# Wrigley_V1.net
KiCad netlist of a schematic drawn in EAGLE
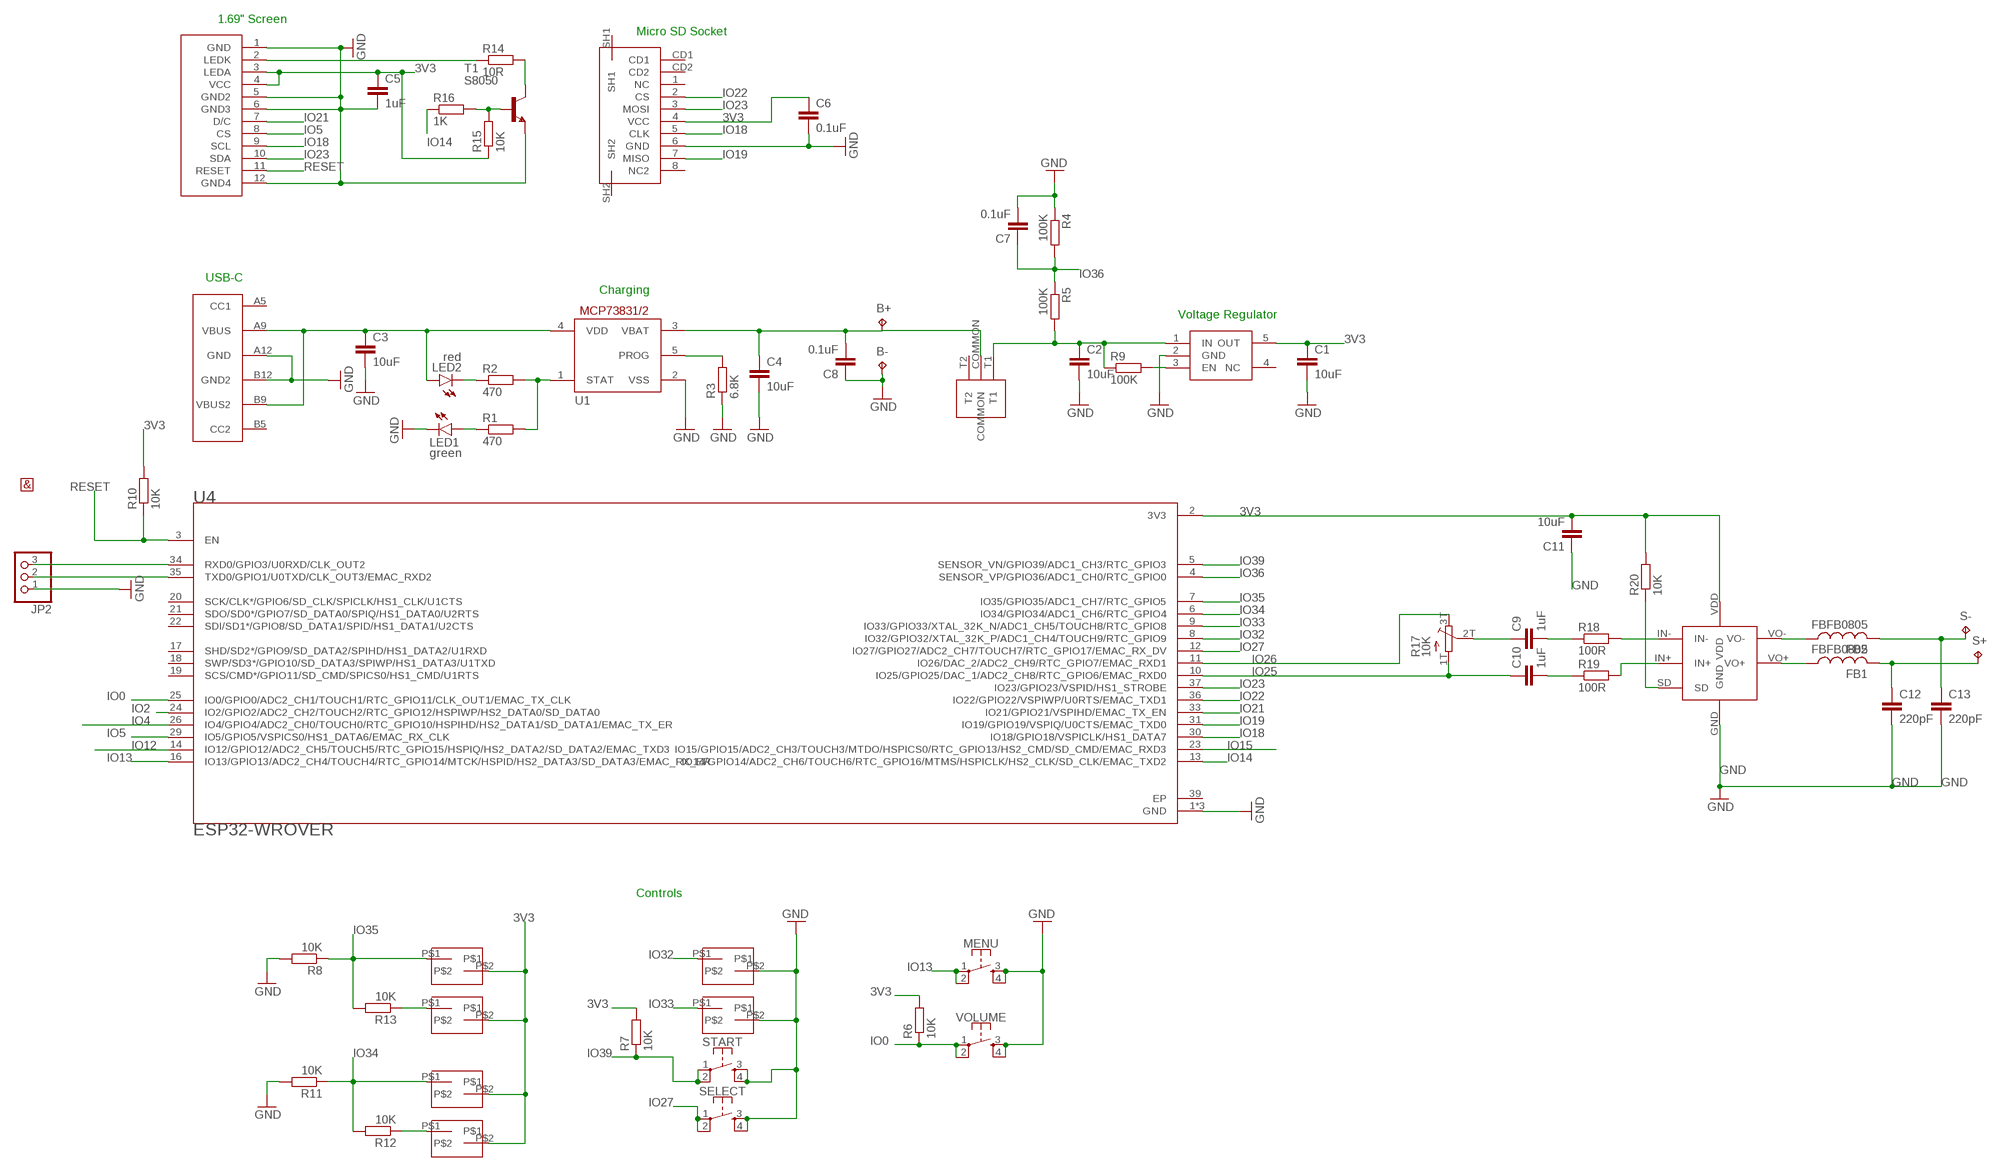
[diagram p0: schematic, sheet 1]

(export (version "E")
  (design (tool "Eeschema 10.0.6"))
  (components
    (comp (ref "A")
      (value "POCKET-BUTTONS-BIG")
      (footprint "eagle-import:POCKET-MEMBRANE-BIG")
      (libsource (lib "eagle-import") (part "POCKET-BUTTONS-BIG"))
    )
    (comp (ref "B")
      (value "POCKET-BUTTONS-BIG")
      (footprint "eagle-import:POCKET-MEMBRANE-BIG")
      (libsource (lib "eagle-import") (part "POCKET-BUTTONS-BIG"))
    )
    (comp (ref "B+")
      (value "TPTP20R")
      (footprint "eagle-import:TP20R")
      (libsource (lib "eagle-import") (part "TPTP20R"))
    )
    (comp (ref "B-")
      (value "TPTP20R")
      (footprint "eagle-import:TP20R")
      (libsource (lib "eagle-import") (part "TPTP20R"))
    )
    (comp (ref "C1")
      (value "10uF")
      (footprint "eagle-import:C0805")
      (libsource (lib "eagle-import") (part "C-EUC0805"))
    )
    (comp (ref "C2")
      (value "10uF")
      (footprint "eagle-import:C0805")
      (libsource (lib "eagle-import") (part "C-EUC0805"))
    )
    (comp (ref "C3")
      (value "10uF")
      (footprint "eagle-import:C0805")
      (libsource (lib "eagle-import") (part "C-EUC0805"))
    )
    (comp (ref "C4")
      (value "10uF")
      (footprint "eagle-import:C0805")
      (libsource (lib "eagle-import") (part "C-EUC0805"))
    )
    (comp (ref "C5")
      (value "1uF")
      (footprint "eagle-import:C0805")
      (libsource (lib "eagle-import") (part "C-EUC0805"))
    )
    (comp (ref "C6")
      (value "0.1uF")
      (footprint "eagle-import:C0805")
      (libsource (lib "eagle-import") (part "C-EUC0805"))
    )
    (comp (ref "C7")
      (value "0.1uF")
      (footprint "eagle-import:C0805")
      (libsource (lib "eagle-import") (part "C-EUC0805"))
    )
    (comp (ref "C8")
      (value "0.1uF")
      (footprint "eagle-import:C0805")
      (libsource (lib "eagle-import") (part "C-EUC0805"))
    )
    (comp (ref "C9")
      (value "1uF")
      (footprint "eagle-import:C0805")
      (libsource (lib "eagle-import") (part "C-EUC0805"))
    )
    (comp (ref "C10")
      (value "1uF")
      (footprint "eagle-import:C0805")
      (libsource (lib "eagle-import") (part "C-EUC0805"))
    )
    (comp (ref "C11")
      (value "10uF")
      (footprint "eagle-import:C0805")
      (libsource (lib "eagle-import") (part "C-EUC0805"))
    )
    (comp (ref "C12")
      (value "220pF")
      (footprint "eagle-import:C0805")
      (libsource (lib "eagle-import") (part "C-EUC0805"))
    )
    (comp (ref "C13")
      (value "220pF")
      (footprint "eagle-import:C0805")
      (libsource (lib "eagle-import") (part "C-EUC0805"))
    )
    (comp (ref "DOWN")
      (value "POCKET-BUTTONS-BIG")
      (footprint "eagle-import:POCKET-MEMBRANE-BIG")
      (libsource (lib "eagle-import") (part "POCKET-BUTTONS-BIG"))
    )
    (comp (ref "FB1")
      (value "FBFB0805")
      (footprint "eagle-import:0805")
      (libsource (lib "eagle-import") (part "FBFB0805"))
    )
    (comp (ref "FB2")
      (value "FBFB0805")
      (footprint "eagle-import:0805")
      (libsource (lib "eagle-import") (part "FBFB0805"))
    )
    (comp (ref "JP2")
      (value "PINHD-1X03_2.54-S")
      (footprint "eagle-import:1X03-S")
      (libsource (lib "eagle-import") (part "PINHD-1X03_2.54-S"))
    )
    (comp (ref "LED1")
      (value "green")
      (footprint "eagle-import:CHIP-LED0805")
      (libsource (lib "eagle-import") (part "LEDCHIP-LED0805"))
    )
    (comp (ref "LED2")
      (value "red")
      (footprint "eagle-import:CHIP-LED0805")
      (libsource (lib "eagle-import") (part "LEDCHIP-LED0805"))
    )
    (comp (ref "LEFT")
      (value "POCKET-BUTTONS-BIG")
      (footprint "eagle-import:POCKET-MEMBRANE-BIG")
      (libsource (lib "eagle-import") (part "POCKET-BUTTONS-BIG"))
    )
    (comp (ref "MENU")
      (value "MOMENTARY-SWITCH-SPST-2-SMD-5.2MM")
      (footprint "eagle-import:TACTILE_SWITCH_SMD_5.2MM")
      (libsource (lib "eagle-import") (part "MOMENTARY-SWITCH-SPST-2-SMD-5.2MM"))
    )
    (comp (ref "R1")
      (value "470")
      (footprint "eagle-import:R0805")
      (libsource (lib "eagle-import") (part "resistor_348_R-EU_R0805"))
    )
    (comp (ref "R2")
      (value "470")
      (footprint "eagle-import:R0805")
      (libsource (lib "eagle-import") (part "resistor_348_R-EU_R0805"))
    )
    (comp (ref "R3")
      (value "6.8K")
      (footprint "eagle-import:R0805")
      (libsource (lib "eagle-import") (part "resistor_348_R-EU_R0805"))
    )
    (comp (ref "R4")
      (value "100K")
      (footprint "eagle-import:M0805")
      (libsource (lib "eagle-import") (part "resistor_348_R-EU_M0805"))
    )
    (comp (ref "R5")
      (value "100K")
      (footprint "eagle-import:M0805")
      (libsource (lib "eagle-import") (part "resistor_348_R-EU_M0805"))
    )
    (comp (ref "R6")
      (value "10K")
      (footprint "eagle-import:M0805")
      (libsource (lib "eagle-import") (part "resistor_348_R-EU_M0805"))
    )
    (comp (ref "R7")
      (value "10K")
      (footprint "eagle-import:M0805")
      (libsource (lib "eagle-import") (part "resistor_348_R-EU_M0805"))
    )
    (comp (ref "R8")
      (value "10K")
      (footprint "eagle-import:M0805")
      (libsource (lib "eagle-import") (part "resistor_348_R-EU_M0805"))
    )
    (comp (ref "R9")
      (value "100K")
      (footprint "eagle-import:M0805")
      (libsource (lib "eagle-import") (part "resistor_348_R-EU_M0805"))
    )
    (comp (ref "R10")
      (value "10K")
      (footprint "eagle-import:M0805")
      (libsource (lib "eagle-import") (part "resistor_348_R-EU_M0805"))
    )
    (comp (ref "R11")
      (value "10K")
      (footprint "eagle-import:M0805")
      (libsource (lib "eagle-import") (part "resistor_348_R-EU_M0805"))
    )
    (comp (ref "R12")
      (value "10K")
      (footprint "eagle-import:M0805")
      (libsource (lib "eagle-import") (part "resistor_348_R-EU_M0805"))
    )
    (comp (ref "R13")
      (value "10K")
      (footprint "eagle-import:M0805")
      (libsource (lib "eagle-import") (part "resistor_348_R-EU_M0805"))
    )
    (comp (ref "R14")
      (value "10R")
      (footprint "eagle-import:M0805")
      (libsource (lib "eagle-import") (part "resistor_348_R-EU_M0805"))
    )
    (comp (ref "R15")
      (value "10K")
      (footprint "eagle-import:M0805")
      (libsource (lib "eagle-import") (part "resistor_348_R-EU_M0805"))
    )
    (comp (ref "R16")
      (value "1K")
      (footprint "eagle-import:M0805")
      (libsource (lib "eagle-import") (part "resistor_348_R-EU_M0805"))
    )
    (comp (ref "R17")
      (value "10K")
      (footprint "eagle-import:SLIDE-POT-RS08U11AZ001")
      (libsource (lib "eagle-import") (part "TRIMPOT"))
    )
    (comp (ref "R18")
      (value "100R")
      (footprint "eagle-import:R0805")
      (libsource (lib "eagle-import") (part "R-EU_R0805"))
    )
    (comp (ref "R19")
      (value "100R")
      (footprint "eagle-import:R0805")
      (libsource (lib "eagle-import") (part "R-EU_R0805"))
    )
    (comp (ref "R20")
      (value "10K")
      (footprint "eagle-import:R0805")
      (libsource (lib "eagle-import") (part "R-EU_R0805"))
    )
    (comp (ref "RIGHT")
      (value "POCKET-BUTTONS-BIG")
      (footprint "eagle-import:POCKET-MEMBRANE-BIG")
      (libsource (lib "eagle-import") (part "POCKET-BUTTONS-BIG"))
    )
    (comp (ref "S+")
      (value "TPTP20R")
      (footprint "eagle-import:TP20R")
      (libsource (lib "eagle-import") (part "TPTP20R"))
    )
    (comp (ref "S-")
      (value "TPTP20R")
      (footprint "eagle-import:TP20R")
      (libsource (lib "eagle-import") (part "TPTP20R"))
    )
    (comp (ref "SELECT")
      (value "MOMENTARY-SWITCH-SPST-2-SMD-5.2MM")
      (footprint "eagle-import:TACTILE_SWITCH_SMD_5.2MM")
      (libsource (lib "eagle-import") (part "MOMENTARY-SWITCH-SPST-2-SMD-5.2MM"))
    )
    (comp (ref "START")
      (value "MOMENTARY-SWITCH-SPST-2-SMD-5.2MM")
      (footprint "eagle-import:TACTILE_SWITCH_SMD_5.2MM")
      (libsource (lib "eagle-import") (part "MOMENTARY-SWITCH-SPST-2-SMD-5.2MM"))
    )
    (comp (ref "T1")
      (value "S8050")
      (footprint "eagle-import:SOT23-BEC")
      (libsource (lib "eagle-import") (part "S8050"))
    )
    (comp (ref "U$1")
      (value "MICROSD-SOCKET-RISTRETTONO-HOLES")
      (footprint "eagle-import:MICROSD-SOCKET-WRIGLEY")
      (libsource (lib "eagle-import") (part "MICROSD-SOCKET-RISTRETTONO-HOLES"))
    )
    (comp (ref "U$3")
      (value "1.69-INCH-SCREEN-ROUNDED")
      (footprint "eagle-import:1.69-INCH-SCREEN-ROUNDED")
      (libsource (lib "eagle-import") (part "1.69-INCH-SCREEN-ROUNDED"))
    )
    (comp (ref "U$5")
      (value "NULL2-SWITCH")
      (footprint "eagle-import:NULL2-SWITCH")
      (libsource (lib "eagle-import") (part "NULL2-SWITCH"))
    )
    (comp (ref "U$8")
      (value "USB-C-6PIN")
      (footprint "eagle-import:USB-C-6PIN")
      (libsource (lib "eagle-import") (part "USB-C-6PIN"))
    )
    (comp (ref "U$9")
      (value "AMP-HALF")
      (footprint "eagle-import:AMP-HALF")
      (libsource (lib "eagle-import") (part "AMP-HALF"))
    )
    (comp (ref "U1")
      (value "MCP73831/OT")
      (footprint "eagle-import:SOT23-5L")
      (libsource (lib "eagle-import") (part "MCP73831/OT"))
    )
    (comp (ref "U2")
      (value "AP2112-REGULATORWRIGLEY")
      (footprint "eagle-import:SOT23-5L")
      (libsource (lib "eagle-import") (part "AP2112-REGULATORWRIGLEY"))
    )
    (comp (ref "U3")
      (value "PAM8302A")
      (footprint "eagle-import:PAM8302A-SOP8")
      (libsource (lib "eagle-import") (part "PAM8302A"))
    )
    (comp (ref "U4")
      (value "ESP32-WROVER")
      (footprint "eagle-import:XCVR-ESP32-WROVER")
      (libsource (lib "eagle-import") (part "ESP32-WROVER"))
    )
    (comp (ref "UP")
      (value "POCKET-BUTTONS-BIG")
      (footprint "eagle-import:POCKET-MEMBRANE-BIG")
      (libsource (lib "eagle-import") (part "POCKET-BUTTONS-BIG"))
    )
    (comp (ref "VOLUME")
      (value "MOMENTARY-SWITCH-SPST-2-SMD-5.2MM")
      (footprint "eagle-import:TACTILE_SWITCH_SMD_5.2MM")
      (libsource (lib "eagle-import") (part "MOMENTARY-SWITCH-SPST-2-SMD-5.2MM"))
    )
  )
  (nets
    (net (code "1") (name "/3V3") (class "Default")
      (node (ref "C1") (pin "1") (pinfunction "1_1") (pintype "passive"))
      (node (ref "C11") (pin "2") (pinfunction "2_2") (pintype "passive"))
      (node (ref "C5") (pin "1") (pinfunction "1_1") (pintype "passive"))
      (node (ref "C6") (pin "1") (pinfunction "1_1") (pintype "passive"))
      (node (ref "DOWN") (pin "P$2") (pinfunction "P$2_P$2") (pintype "bidirectional"))
      (node (ref "LEFT") (pin "P$2") (pinfunction "P$2_P$2") (pintype "bidirectional"))
      (node (ref "R10") (pin "2") (pinfunction "2_2") (pintype "passive"))
      (node (ref "R15") (pin "1") (pinfunction "1_1") (pintype "passive"))
      (node (ref "R20") (pin "2") (pinfunction "2_2") (pintype "passive"))
      (node (ref "R6") (pin "2") (pinfunction "2_2") (pintype "passive"))
      (node (ref "R7") (pin "2") (pinfunction "2_2") (pintype "passive"))
      (node (ref "RIGHT") (pin "P$2") (pinfunction "P$2_P$2") (pintype "bidirectional"))
      (node (ref "U$1") (pin "4") (pinfunction "VCC_4") (pintype "bidirectional"))
      (node (ref "U$3") (pin "3") (pinfunction "LEDA_3") (pintype "bidirectional"))
      (node (ref "U$3") (pin "4") (pinfunction "VCC_4") (pintype "bidirectional"))
      (node (ref "U2") (pin "5") (pinfunction "OUT_5") (pintype "bidirectional"))
      (node (ref "U3") (pin "VDD") (pinfunction "VDD_VDD") (pintype "bidirectional"))
      (node (ref "U4") (pin "2") (pinfunction "3V3_2") (pintype "power_in"))
      (node (ref "UP") (pin "P$2") (pinfunction "P$2_P$2") (pintype "bidirectional"))
    )
    (net (code "2") (name "/EP") (class "Default")
      (node (ref "U4") (pin "39") (pinfunction "EP_39") (pintype "power_in"))
    )
    (net (code "3") (name "/IO0") (class "Default")
      (node (ref "R6") (pin "1") (pinfunction "1_1") (pintype "passive"))
      (node (ref "U4") (pin "25") (pinfunction "IO0/GPIO0/ADC2_CH1/TOUCH1/RTC_GPIO11/CLK_OUT1/EMAC_TX_CLK_25") (pintype "bidirectional"))
      (node (ref "VOLUME") (pin "1") (pinfunction "1_1") (pintype "passive"))
      (node (ref "VOLUME") (pin "2") (pinfunction "2_2") (pintype "passive"))
    )
    (net (code "4") (name "/IO2") (class "Default")
      (node (ref "U4") (pin "24") (pinfunction "IO2/GPIO2/ADC2_CH2/TOUCH2/RTC_GPIO12/HSPIWP/HS2_DATA0/SD_DATA0_24") (pintype "bidirectional"))
    )
    (net (code "5") (name "/IO4") (class "Default")
      (node (ref "U4") (pin "26") (pinfunction "IO4/GPIO4/ADC2_CH0/TOUCH0/RTC_GPIO10/HSPIHD/HS2_DATA1/SD_DATA1/EMAC_TX_ER_26") (pintype "bidirectional"))
    )
    (net (code "6") (name "/IO5") (class "Default")
      (node (ref "U$3") (pin "8") (pinfunction "CS_8") (pintype "bidirectional"))
      (node (ref "U4") (pin "29") (pinfunction "IO5/GPIO5/VSPICS0/HS1_DATA6/EMAC_RX_CLK_29") (pintype "bidirectional"))
    )
    (net (code "7") (name "/IO12") (class "Default")
      (node (ref "U4") (pin "14") (pinfunction "IO12/GPIO12/ADC2_CH5/TOUCH5/RTC_GPIO15/HSPIQ/HS2_DATA2/SD_DATA2/EMAC_TXD3_14") (pintype "bidirectional"))
    )
    (net (code "8") (name "/IO13") (class "Default")
      (node (ref "MENU") (pin "1") (pinfunction "1_1") (pintype "passive"))
      (node (ref "MENU") (pin "2") (pinfunction "2_2") (pintype "passive"))
      (node (ref "U4") (pin "16") (pinfunction "IO13/GPIO13/ADC2_CH4/TOUCH4/RTC_GPIO14/MTCK/HSPID/HS2_DATA3/SD_DATA3/EMAC_RX_ER_16") (pintype "bidirectional"))
    )
    (net (code "9") (name "/IO14") (class "Default")
      (node (ref "R16") (pin "1") (pinfunction "1_1") (pintype "passive"))
      (node (ref "U4") (pin "13") (pinfunction "IO14/GPIO14/ADC2_CH6/TOUCH6/RTC_GPIO16/MTMS/HSPICLK/HS2_CLK/SD_CLK/EMAC_TXD2_13") (pintype "bidirectional"))
    )
    (net (code "10") (name "/IO15") (class "Default")
      (node (ref "U4") (pin "23") (pinfunction "IO15/GPIO15/ADC2_CH3/TOUCH3/MTDO/HSPICS0/RTC_GPIO13/HS2_CMD/SD_CMD/EMAC_RXD3_23") (pintype "bidirectional"))
    )
    (net (code "11") (name "/IO18") (class "Default")
      (node (ref "U$1") (pin "5") (pinfunction "CLK_5") (pintype "bidirectional"))
      (node (ref "U$3") (pin "9") (pinfunction "SCL_9") (pintype "bidirectional"))
      (node (ref "U4") (pin "30") (pinfunction "IO18/GPIO18/VSPICLK/HS1_DATA7_30") (pintype "bidirectional"))
    )
    (net (code "12") (name "/IO19") (class "Default")
      (node (ref "U$1") (pin "7") (pinfunction "MISO_7") (pintype "bidirectional"))
      (node (ref "U4") (pin "31") (pinfunction "IO19/GPIO19/VSPIQ/U0CTS/EMAC_TXD0_31") (pintype "bidirectional"))
    )
    (net (code "13") (name "/IO21") (class "Default")
      (node (ref "U$3") (pin "7") (pinfunction "D/C_7") (pintype "bidirectional"))
      (node (ref "U4") (pin "33") (pinfunction "IO21/GPIO21/VSPIHD/EMAC_TX_EN_33") (pintype "bidirectional"))
    )
    (net (code "14") (name "/IO22") (class "Default")
      (node (ref "U$1") (pin "2") (pinfunction "CS_2") (pintype "bidirectional"))
      (node (ref "U4") (pin "36") (pinfunction "IO22/GPIO22/VSPIWP/U0RTS/EMAC_TXD1_36") (pintype "bidirectional"))
    )
    (net (code "15") (name "/IO23") (class "Default")
      (node (ref "U$1") (pin "3") (pinfunction "MOSI_3") (pintype "bidirectional"))
      (node (ref "U$3") (pin "10") (pinfunction "SDA_10") (pintype "bidirectional"))
      (node (ref "U4") (pin "37") (pinfunction "IO23/GPIO23/VSPID/HS1_STROBE_37") (pintype "bidirectional"))
    )
    (net (code "16") (name "/IO25") (class "Default")
      (node (ref "C10") (pin "1") (pinfunction "1_1") (pintype "passive"))
      (node (ref "R17") (pin "1T") (pinfunction "1_1T") (pintype "passive"))
      (node (ref "U4") (pin "10") (pinfunction "IO25/GPIO25/DAC_1/ADC2_CH8/RTC_GPIO6/EMAC_RXD0_10") (pintype "bidirectional"))
    )
    (net (code "17") (name "/IO26") (class "Default")
      (node (ref "R17") (pin "3T") (pinfunction "3_3T") (pintype "passive"))
      (node (ref "U4") (pin "11") (pinfunction "IO26/DAC_2/ADC2_CH9/RTC_GPIO7/EMAC_RXD1_11") (pintype "bidirectional"))
    )
    (net (code "18") (name "/IO27") (class "Default")
      (node (ref "SELECT") (pin "1") (pinfunction "1_1") (pintype "passive"))
      (node (ref "SELECT") (pin "2") (pinfunction "2_2") (pintype "passive"))
      (node (ref "U4") (pin "12") (pinfunction "IO27/GPIO27/ADC2_CH7/TOUCH7/RTC_GPIO17/EMAC_RX_DV_12") (pintype "bidirectional"))
    )
    (net (code "19") (name "/IO32") (class "Default")
      (node (ref "A") (pin "P$1") (pinfunction "P$1_P$1") (pintype "bidirectional"))
      (node (ref "U4") (pin "8") (pinfunction "IO32/GPIO32/XTAL_32K_P/ADC1_CH4/TOUCH9/RTC_GPIO9_8") (pintype "bidirectional"))
    )
    (net (code "20") (name "/IO33") (class "Default")
      (node (ref "B") (pin "P$1") (pinfunction "P$1_P$1") (pintype "bidirectional"))
      (node (ref "U4") (pin "9") (pinfunction "IO33/GPIO33/XTAL_32K_N/ADC1_CH5/TOUCH8/RTC_GPIO8_9") (pintype "bidirectional"))
    )
    (net (code "21") (name "/IO34") (class "Default")
      (node (ref "LEFT") (pin "P$1") (pinfunction "P$1_P$1") (pintype "bidirectional"))
      (node (ref "R11") (pin "1") (pinfunction "1_1") (pintype "passive"))
      (node (ref "R12") (pin "2") (pinfunction "2_2") (pintype "passive"))
      (node (ref "U4") (pin "6") (pinfunction "IO34/GPIO34/ADC1_CH6/RTC_GPIO4_6") (pintype "bidirectional"))
    )
    (net (code "22") (name "/IO35") (class "Default")
      (node (ref "R13") (pin "2") (pinfunction "2_2") (pintype "passive"))
      (node (ref "R8") (pin "1") (pinfunction "1_1") (pintype "passive"))
      (node (ref "U4") (pin "7") (pinfunction "IO35/GPIO35/ADC1_CH7/RTC_GPIO5_7") (pintype "bidirectional"))
      (node (ref "UP") (pin "P$1") (pinfunction "P$1_P$1") (pintype "bidirectional"))
    )
    (net (code "23") (name "/IO36") (class "Default")
      (node (ref "C7") (pin "1") (pinfunction "1_1") (pintype "passive"))
      (node (ref "R4") (pin "2") (pinfunction "2_2") (pintype "passive"))
      (node (ref "R5") (pin "1") (pinfunction "1_1") (pintype "passive"))
      (node (ref "U4") (pin "4") (pinfunction "SENSOR_VP/GPIO36/ADC1_CH0/RTC_GPIO0_4") (pintype "bidirectional"))
    )
    (net (code "24") (name "/IO39") (class "Default")
      (node (ref "R7") (pin "1") (pinfunction "1_1") (pintype "passive"))
      (node (ref "START") (pin "1") (pinfunction "1_1") (pintype "passive"))
      (node (ref "START") (pin "2") (pinfunction "2_2") (pintype "passive"))
      (node (ref "U4") (pin "5") (pinfunction "SENSOR_VN/GPIO39/ADC1_CH3/RTC_GPIO3_5") (pintype "bidirectional"))
    )
    (net (code "25") (name "/RESET") (class "Default")
      (node (ref "R10") (pin "1") (pinfunction "1_1") (pintype "passive"))
      (node (ref "U$3") (pin "11") (pinfunction "RESET_11") (pintype "bidirectional"))
      (node (ref "U4") (pin "3") (pinfunction "EN_3") (pintype "input"))
    )
    (net (code "26") (name "GND") (class "Default")
      (node (ref "A") (pin "P$2") (pinfunction "P$2_P$2") (pintype "bidirectional"))
      (node (ref "B") (pin "P$2") (pinfunction "P$2_P$2") (pintype "bidirectional"))
      (node (ref "B-") (pin "TP") (pinfunction "TP_TP") (pintype "input"))
      (node (ref "C1") (pin "2") (pinfunction "2_2") (pintype "passive"))
      (node (ref "C11") (pin "1") (pinfunction "1_1") (pintype "passive"))
      (node (ref "C12") (pin "2") (pinfunction "2_2") (pintype "passive"))
      (node (ref "C13") (pin "2") (pinfunction "2_2") (pintype "passive"))
      (node (ref "C2") (pin "2") (pinfunction "2_2") (pintype "passive"))
      (node (ref "C3") (pin "2") (pinfunction "2_2") (pintype "passive"))
      (node (ref "C4") (pin "2") (pinfunction "2_2") (pintype "passive"))
      (node (ref "C5") (pin "2") (pinfunction "2_2") (pintype "passive"))
      (node (ref "C6") (pin "2") (pinfunction "2_2") (pintype "passive"))
      (node (ref "C7") (pin "2") (pinfunction "2_2") (pintype "passive"))
      (node (ref "C8") (pin "1") (pinfunction "1_1") (pintype "passive"))
      (node (ref "JP2") (pin "1") (pinfunction "1_1") (pintype "passive"))
      (node (ref "LED1") (pin "C") (pinfunction "C_C") (pintype "passive"))
      (node (ref "MENU") (pin "3") (pinfunction "3_3") (pintype "passive"))
      (node (ref "MENU") (pin "4") (pinfunction "4_4") (pintype "passive"))
      (node (ref "R11") (pin "2") (pinfunction "2_2") (pintype "passive"))
      (node (ref "R3") (pin "1") (pinfunction "1_1") (pintype "passive"))
      (node (ref "R4") (pin "1") (pinfunction "1_1") (pintype "passive"))
      (node (ref "R8") (pin "2") (pinfunction "2_2") (pintype "passive"))
      (node (ref "SELECT") (pin "3") (pinfunction "3_3") (pintype "passive"))
      (node (ref "SELECT") (pin "4") (pinfunction "4_4") (pintype "passive"))
      (node (ref "START") (pin "3") (pinfunction "3_3") (pintype "passive"))
      (node (ref "START") (pin "4") (pinfunction "4_4") (pintype "passive"))
      (node (ref "T1") (pin "E") (pinfunction "E_E") (pintype "passive"))
      (node (ref "U$1") (pin "6") (pinfunction "GND_6") (pintype "bidirectional"))
      (node (ref "U$3") (pin "1") (pinfunction "GND_1") (pintype "bidirectional"))
      (node (ref "U$3") (pin "12") (pinfunction "GND4_12") (pintype "bidirectional"))
      (node (ref "U$3") (pin "5") (pinfunction "GND2_5") (pintype "bidirectional"))
      (node (ref "U$3") (pin "6") (pinfunction "GND3_6") (pintype "bidirectional"))
      (node (ref "U$8") (pin "A12") (pinfunction "GND_A12") (pintype "bidirectional"))
      (node (ref "U$8") (pin "B12") (pinfunction "GND2_B12") (pintype "bidirectional"))
      (node (ref "U1") (pin "2") (pinfunction "VSS_2") (pintype "power_in"))
      (node (ref "U2") (pin "2") (pinfunction "GND_2") (pintype "bidirectional"))
      (node (ref "U3") (pin "GND") (pinfunction "GND_GND") (pintype "bidirectional"))
      (node (ref "U4") (pin "1") (pinfunction "GND_1") (pintype "power_in"))
      (node (ref "U4") (pin "15") (pinfunction "GND_15") (pintype "power_in"))
      (node (ref "U4") (pin "38") (pinfunction "GND_38") (pintype "power_in"))
      (node (ref "VOLUME") (pin "3") (pinfunction "3_3") (pintype "passive"))
      (node (ref "VOLUME") (pin "4") (pinfunction "4_4") (pintype "passive"))
    )
    (net (code "27") (name "Net-(C9-Pad2)") (class "Default")
      (node (ref "C9") (pin "2") (pinfunction "2_2") (pintype "passive"))
      (node (ref "R18") (pin "1") (pinfunction "1_1") (pintype "passive"))
    )
    (net (code "28") (name "Net-(C10-Pad2)") (class "Default")
      (node (ref "C10") (pin "2") (pinfunction "2_2") (pintype "passive"))
      (node (ref "R19") (pin "1") (pinfunction "1_1") (pintype "passive"))
    )
    (net (code "29") (name "Net-(C12-Pad1)") (class "Default")
      (node (ref "C12") (pin "1") (pinfunction "1_1") (pintype "passive"))
      (node (ref "FB1") (pin "2") (pinfunction "2_2") (pintype "passive"))
      (node (ref "S+") (pin "TP") (pinfunction "TP_TP") (pintype "input"))
    )
    (net (code "30") (name "Net-(C13-Pad1)") (class "Default")
      (node (ref "C13") (pin "1") (pinfunction "1_1") (pintype "passive"))
      (node (ref "FB2") (pin "2") (pinfunction "2_2") (pintype "passive"))
      (node (ref "S-") (pin "TP") (pinfunction "TP_TP") (pintype "input"))
    )
    (net (code "31") (name "Net-(DOWN-PadP$1)") (class "Default")
      (node (ref "DOWN") (pin "P$1") (pinfunction "P$1_P$1") (pintype "bidirectional"))
      (node (ref "R13") (pin "1") (pinfunction "1_1") (pintype "passive"))
    )
    (net (code "32") (name "Net-(FB1-Pad1)") (class "Default")
      (node (ref "FB1") (pin "1") (pinfunction "1_1") (pintype "passive"))
      (node (ref "U3") (pin "VO+") (pinfunction "VO+_VO+") (pintype "bidirectional"))
    )
    (net (code "33") (name "Net-(FB2-Pad1)") (class "Default")
      (node (ref "FB2") (pin "1") (pinfunction "1_1") (pintype "passive"))
      (node (ref "U3") (pin "VO-") (pinfunction "VO-_VO-") (pintype "bidirectional"))
    )
    (net (code "34") (name "Net-(LED1-PadA)") (class "Default")
      (node (ref "LED1") (pin "A") (pinfunction "A_A") (pintype "passive"))
      (node (ref "R1") (pin "1") (pinfunction "1_1") (pintype "passive"))
    )
    (net (code "35") (name "Net-(LED2-PadC)") (class "Default")
      (node (ref "LED2") (pin "C") (pinfunction "C_C") (pintype "passive"))
      (node (ref "R2") (pin "1") (pinfunction "1_1") (pintype "passive"))
    )
    (net (code "36") (name "Net-(R12-Pad1)") (class "Default")
      (node (ref "R12") (pin "1") (pinfunction "1_1") (pintype "passive"))
      (node (ref "RIGHT") (pin "P$1") (pinfunction "P$1_P$1") (pintype "bidirectional"))
    )
    (net (code "37") (name "Net-(R14-Pad2)") (class "Default")
      (node (ref "R14") (pin "2") (pinfunction "2_2") (pintype "passive"))
      (node (ref "T1") (pin "C") (pinfunction "C_C") (pintype "passive"))
    )
    (net (code "38") (name "Net-(R15-Pad2)") (class "Default")
      (node (ref "R15") (pin "2") (pinfunction "2_2") (pintype "passive"))
      (node (ref "R16") (pin "2") (pinfunction "2_2") (pintype "passive"))
      (node (ref "T1") (pin "B") (pinfunction "B_B") (pintype "passive"))
    )
    (net (code "39") (name "Net-(R17-2)") (class "Default")
      (node (ref "C9") (pin "1") (pinfunction "1_1") (pintype "passive"))
      (node (ref "R17") (pin "2T") (pinfunction "2_2T") (pintype "passive"))
    )
    (net (code "40") (name "Net-(R18-Pad2)") (class "Default")
      (node (ref "R18") (pin "2") (pinfunction "2_2") (pintype "passive"))
      (node (ref "U3") (pin "IN-") (pinfunction "IN-_IN-") (pintype "bidirectional"))
    )
    (net (code "41") (name "Net-(R19-Pad2)") (class "Default")
      (node (ref "R19") (pin "2") (pinfunction "2_2") (pintype "passive"))
      (node (ref "U3") (pin "IN+") (pinfunction "IN+_IN+") (pintype "bidirectional"))
    )
    (net (code "42") (name "Net-(R20-Pad1)") (class "Default")
      (node (ref "R20") (pin "1") (pinfunction "1_1") (pintype "passive"))
      (node (ref "U3") (pin "SD") (pinfunction "SD_SD") (pintype "bidirectional"))
    )
    (net (code "43") (name "Net-(U$3-LEDK)") (class "Default")
      (node (ref "R14") (pin "1") (pinfunction "1_1") (pintype "passive"))
      (node (ref "U$3") (pin "2") (pinfunction "LEDK_2") (pintype "bidirectional"))
    )
    (net (code "44") (name "Net-(U$8-VBUS)") (class "Default")
      (node (ref "C3") (pin "1") (pinfunction "1_1") (pintype "passive"))
      (node (ref "LED2") (pin "A") (pinfunction "A_A") (pintype "passive"))
      (node (ref "U$8") (pin "A9") (pinfunction "VBUS_A9") (pintype "bidirectional"))
      (node (ref "U$8") (pin "B9") (pinfunction "VBUS2_B9") (pintype "bidirectional"))
      (node (ref "U1") (pin "4") (pinfunction "VDD_4") (pintype "power_in"))
    )
    (net (code "45") (name "Net-(U1-PROG)") (class "Default")
      (node (ref "R3") (pin "2") (pinfunction "2_2") (pintype "passive"))
      (node (ref "U1") (pin "5") (pinfunction "PROG_5") (pintype "input"))
    )
    (net (code "46") (name "Net-(U1-STAT)") (class "Default")
      (node (ref "R1") (pin "2") (pinfunction "2_2") (pintype "passive"))
      (node (ref "R2") (pin "2") (pinfunction "2_2") (pintype "passive"))
      (node (ref "U1") (pin "1") (pinfunction "STAT_1") (pintype "output"))
    )
    (net (code "47") (name "Net-(U1-VBAT)") (class "Default")
      (node (ref "B+") (pin "TP") (pinfunction "TP_TP") (pintype "input"))
      (node (ref "C4") (pin "1") (pinfunction "1_1") (pintype "passive"))
      (node (ref "C8") (pin "2") (pinfunction "2_2") (pintype "passive"))
      (node (ref "U$5") (pin "COMMON") (pinfunction "COMMON_COMMON") (pintype "bidirectional"))
      (node (ref "U1") (pin "3") (pinfunction "VBAT_3") (pintype "bidirectional"))
    )
    (net (code "48") (name "Net-(U2-EN)") (class "Default")
      (node (ref "R9") (pin "2") (pinfunction "2_2") (pintype "passive"))
      (node (ref "U2") (pin "3") (pinfunction "EN_3") (pintype "bidirectional"))
    )
    (net (code "49") (name "Net-(U2-IN)") (class "Default")
      (node (ref "C2") (pin "1") (pinfunction "1_1") (pintype "passive"))
      (node (ref "R5") (pin "2") (pinfunction "2_2") (pintype "passive"))
      (node (ref "R9") (pin "1") (pinfunction "1_1") (pintype "passive"))
      (node (ref "U$5") (pin "T1") (pinfunction "T1_T1") (pintype "bidirectional"))
      (node (ref "U2") (pin "1") (pinfunction "IN_1") (pintype "bidirectional"))
    )
    (net (code "50") (name "Net-(U4-RXD0{slash}GPIO3{slash}U0RXD{slash}CLK_OUT2)") (class "Default")
      (node (ref "JP2") (pin "3") (pinfunction "3_3") (pintype "passive"))
      (node (ref "U4") (pin "34") (pinfunction "RXD0/GPIO3/U0RXD/CLK_OUT2_34") (pintype "bidirectional"))
    )
    (net (code "51") (name "Net-(U4-TXD0{slash}GPIO1{slash}U0TXD{slash}CLK_OUT3{slash}EMAC_RXD2)") (class "Default")
      (node (ref "JP2") (pin "2") (pinfunction "2_2") (pintype "passive"))
      (node (ref "U4") (pin "35") (pinfunction "TXD0/GPIO1/U0TXD/CLK_OUT3/EMAC_RXD2_35") (pintype "bidirectional"))
    )
    (net (code "52") (name "unconnected-(U$1-NC-Pad1)") (class "Default")
      (node (ref "U$1") (pin "1") (pinfunction "NC_1") (pintype "bidirectional"))
    )
    (net (code "53") (name "unconnected-(U$1-NC2-Pad8)") (class "Default")
      (node (ref "U$1") (pin "8") (pinfunction "NC2_8") (pintype "bidirectional"))
    )
    (net (code "54") (name "unconnected-(U$1-PadCD1)") (class "Default")
      (node (ref "U$1") (pin "CD1") (pinfunction "CD1_CD1") (pintype "bidirectional"))
    )
    (net (code "55") (name "unconnected-(U$1-PadCD2)") (class "Default")
      (node (ref "U$1") (pin "CD2") (pinfunction "CD2_CD2") (pintype "bidirectional"))
    )
    (net (code "56") (name "unconnected-(U$1-PadSH1)") (class "Default")
      (node (ref "U$1") (pin "SH1") (pinfunction "SH1_SH1") (pintype "bidirectional"))
    )
    (net (code "57") (name "unconnected-(U$1-PadSH2)") (class "Default")
      (node (ref "U$1") (pin "SH2") (pinfunction "SH2_SH2") (pintype "bidirectional"))
    )
    (net (code "58") (name "unconnected-(U$5-PadT2)") (class "Default")
      (node (ref "U$5") (pin "T2") (pinfunction "T2_T2") (pintype "bidirectional"))
    )
    (net (code "59") (name "unconnected-(U$8-CC1-PadA5)") (class "Default")
      (node (ref "U$8") (pin "A5") (pinfunction "CC1_A5") (pintype "bidirectional"))
    )
    (net (code "60") (name "unconnected-(U$8-CC2-PadB5)") (class "Default")
      (node (ref "U$8") (pin "B5") (pinfunction "CC2_B5") (pintype "bidirectional"))
    )
    (net (code "61") (name "unconnected-(U2-NC-Pad4)") (class "Default")
      (node (ref "U2") (pin "4") (pinfunction "NC_4") (pintype "bidirectional"))
    )
    (net (code "62") (name "unconnected-(U4-SCK{slash}CLK*{slash}GPIO6{slash}SD_CLK{slash}SPICLK{slash}HS1_CLK{slash}U1CTS-Pad20)") (class "Default")
      (node (ref "U4") (pin "20") (pinfunction "SCK/CLK*/GPIO6/SD_CLK/SPICLK/HS1_CLK/U1CTS_20") (pintype "bidirectional"))
    )
    (net (code "63") (name "unconnected-(U4-SCS{slash}CMD*{slash}GPIO11{slash}SD_CMD{slash}SPICS0{slash}HS1_CMD{slash}U1RTS-Pad19)") (class "Default")
      (node (ref "U4") (pin "19") (pinfunction "SCS/CMD*/GPIO11/SD_CMD/SPICS0/HS1_CMD/U1RTS_19") (pintype "bidirectional"))
    )
    (net (code "64") (name "unconnected-(U4-SDI{slash}SD1*{slash}GPIO8{slash}SD_DATA1{slash}SPID{slash}HS1_DATA1{slash}U2CTS-Pad22)") (class "Default")
      (node (ref "U4") (pin "22") (pinfunction "SDI/SD1*/GPIO8/SD_DATA1/SPID/HS1_DATA1/U2CTS_22") (pintype "bidirectional"))
    )
    (net (code "65") (name "unconnected-(U4-SDO{slash}SD0*{slash}GPIO7{slash}SD_DATA0{slash}SPIQ{slash}HS1_DATA0{slash}U2RTS-Pad21)") (class "Default")
      (node (ref "U4") (pin "21") (pinfunction "SDO/SD0*/GPIO7/SD_DATA0/SPIQ/HS1_DATA0/U2RTS_21") (pintype "bidirectional"))
    )
    (net (code "66") (name "unconnected-(U4-SHD{slash}SD2*{slash}GPIO9{slash}SD_DATA2{slash}SPIHD{slash}HS1_DATA2{slash}U1RXD-Pad17)") (class "Default")
      (node (ref "U4") (pin "17") (pinfunction "SHD/SD2*/GPIO9/SD_DATA2/SPIHD/HS1_DATA2/U1RXD_17") (pintype "bidirectional"))
    )
    (net (code "67") (name "unconnected-(U4-SWP{slash}SD3*{slash}GPIO10{slash}SD_DATA3{slash}SPIWP{slash}HS1_DATA3{slash}U1TXD-Pad18)") (class "Default")
      (node (ref "U4") (pin "18") (pinfunction "SWP/SD3*/GPIO10/SD_DATA3/SPIWP/HS1_DATA3/U1TXD_18") (pintype "bidirectional"))
    )
  )
)
